# H-00488_-_Ethernet_Switch.net
KiCad netlist of a schematic drawn in Altium Designer
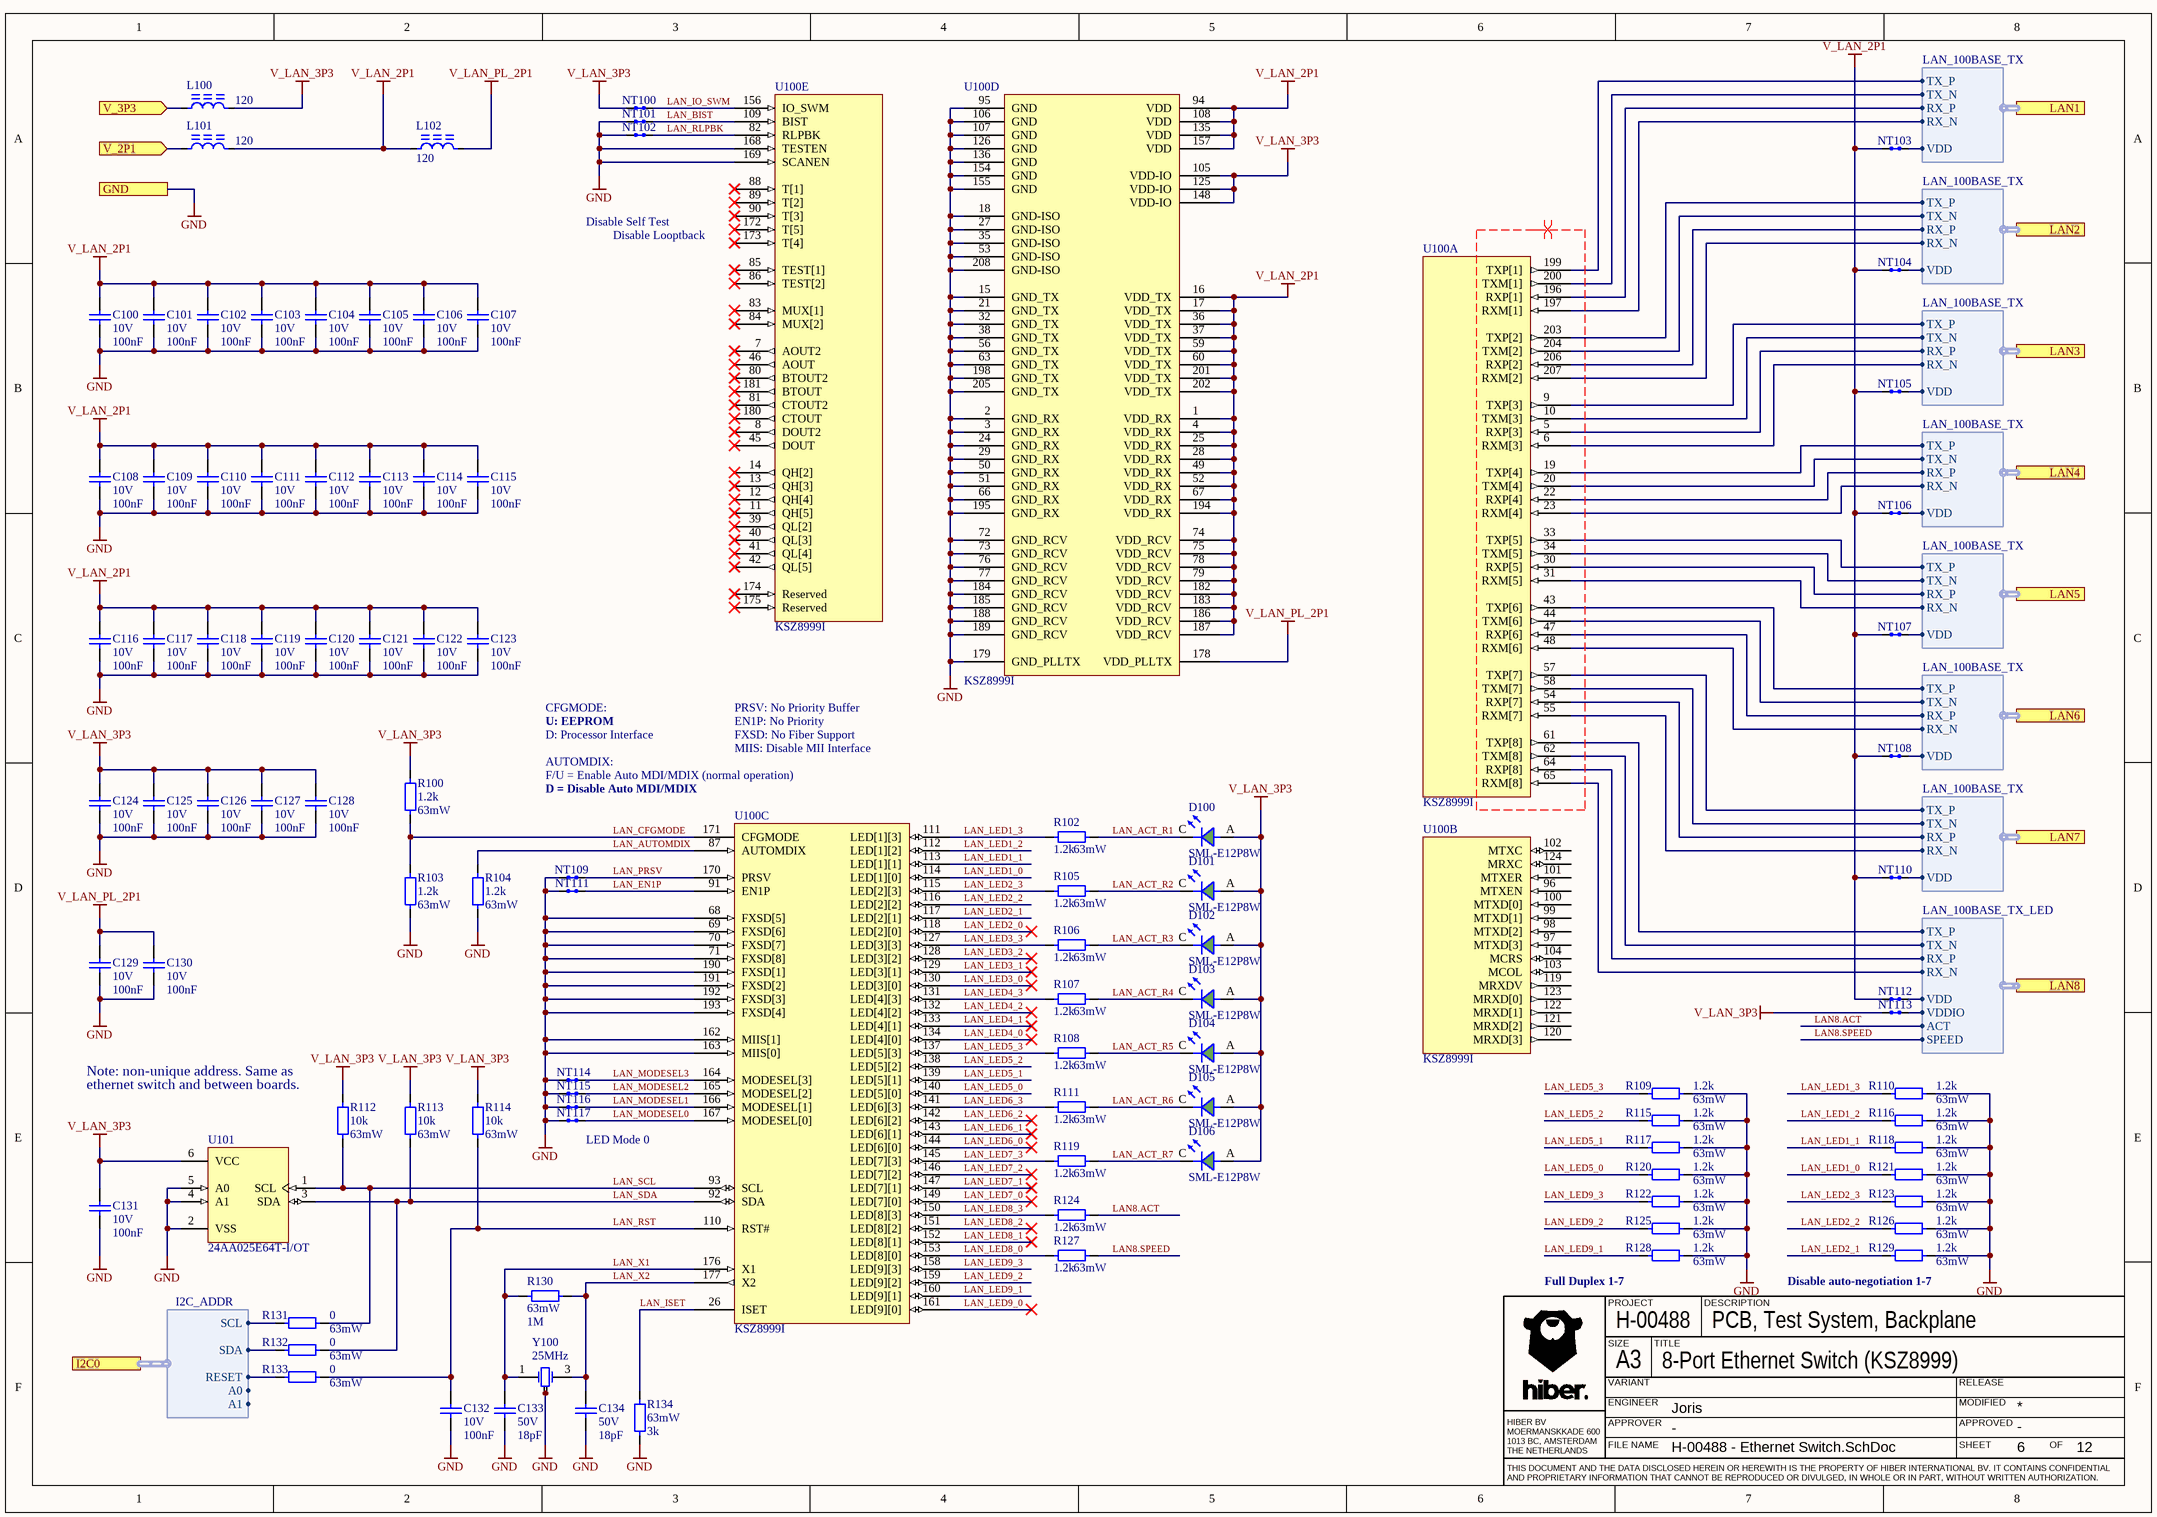
[diagram p0: H-00488 - Ethernet Switch.SchDoc]

(export (version "E")
  (design (tool "Eeschema 10.0.6"))
  (components
    (comp (ref "C100")
      (value "100nF")
      (footprint "CAPC100X50X55L30N")
      (description "CAP Standard 0402 (1005) 100,0nF 10V X7R (Standard)")
      (fields
        (field (name "RATED VOLTAGE") "10V")
        (field (name "TOLERANCE") "10%")
        (field (name "Comment") "C0402C104K8RACTU")
      )
      (libsource (lib "Hiber Vault") (part "CAPACITOR"))
    )
    (comp (ref "C101")
      (value "100nF")
      (footprint "CAPC100X50X55L30N")
      (description "CAP Standard 0402 (1005) 100,0nF 10V X7R (Standard)")
      (fields
        (field (name "RATED VOLTAGE") "10V")
        (field (name "TOLERANCE") "10%")
        (field (name "Comment") "C0402C104K8RACTU")
      )
      (libsource (lib "Hiber Vault") (part "CAPACITOR"))
    )
    (comp (ref "C102")
      (value "100nF")
      (footprint "CAPC100X50X55L30N")
      (description "CAP Standard 0402 (1005) 100,0nF 10V X7R (Standard)")
      (fields
        (field (name "RATED VOLTAGE") "10V")
        (field (name "TOLERANCE") "10%")
        (field (name "Comment") "C0402C104K8RACTU")
      )
      (libsource (lib "Hiber Vault") (part "CAPACITOR"))
    )
    (comp (ref "C103")
      (value "100nF")
      (footprint "CAPC100X50X55L30N")
      (description "CAP Standard 0402 (1005) 100,0nF 10V X7R (Standard)")
      (fields
        (field (name "RATED VOLTAGE") "10V")
        (field (name "TOLERANCE") "10%")
        (field (name "Comment") "C0402C104K8RACTU")
      )
      (libsource (lib "Hiber Vault") (part "CAPACITOR"))
    )
    (comp (ref "C104")
      (value "100nF")
      (footprint "CAPC100X50X55L30N")
      (description "CAP Standard 0402 (1005) 100,0nF 10V X7R (Standard)")
      (fields
        (field (name "RATED VOLTAGE") "10V")
        (field (name "TOLERANCE") "10%")
        (field (name "Comment") "C0402C104K8RACTU")
      )
      (libsource (lib "Hiber Vault") (part "CAPACITOR"))
    )
    (comp (ref "C105")
      (value "100nF")
      (footprint "CAPC100X50X55L30N")
      (description "CAP Standard 0402 (1005) 100,0nF 10V X7R (Standard)")
      (fields
        (field (name "RATED VOLTAGE") "10V")
        (field (name "TOLERANCE") "10%")
        (field (name "Comment") "C0402C104K8RACTU")
      )
      (libsource (lib "Hiber Vault") (part "CAPACITOR"))
    )
    (comp (ref "C106")
      (value "100nF")
      (footprint "CAPC100X50X55L30N")
      (description "CAP Standard 0402 (1005) 100,0nF 10V X7R (Standard)")
      (fields
        (field (name "RATED VOLTAGE") "10V")
        (field (name "TOLERANCE") "10%")
        (field (name "Comment") "C0402C104K8RACTU")
      )
      (libsource (lib "Hiber Vault") (part "CAPACITOR"))
    )
    (comp (ref "C107")
      (value "100nF")
      (footprint "CAPC100X50X55L30N")
      (description "CAP Standard 0402 (1005) 100,0nF 10V X7R (Standard)")
      (fields
        (field (name "RATED VOLTAGE") "10V")
        (field (name "TOLERANCE") "10%")
        (field (name "Comment") "C0402C104K8RACTU")
      )
      (libsource (lib "Hiber Vault") (part "CAPACITOR"))
    )
    (comp (ref "C108")
      (value "100nF")
      (footprint "CAPC100X50X55L30N")
      (description "CAP Standard 0402 (1005) 100,0nF 10V X7R (Standard)")
      (fields
        (field (name "RATED VOLTAGE") "10V")
        (field (name "TOLERANCE") "10%")
        (field (name "Comment") "C0402C104K8RACTU")
      )
      (libsource (lib "Hiber Vault") (part "CAPACITOR"))
    )
    (comp (ref "C109")
      (value "100nF")
      (footprint "CAPC100X50X55L30N")
      (description "CAP Standard 0402 (1005) 100,0nF 10V X7R (Standard)")
      (fields
        (field (name "RATED VOLTAGE") "10V")
        (field (name "TOLERANCE") "10%")
        (field (name "Comment") "C0402C104K8RACTU")
      )
      (libsource (lib "Hiber Vault") (part "CAPACITOR"))
    )
    (comp (ref "C110")
      (value "100nF")
      (footprint "CAPC100X50X55L30N")
      (description "CAP Standard 0402 (1005) 100,0nF 10V X7R (Standard)")
      (fields
        (field (name "RATED VOLTAGE") "10V")
        (field (name "TOLERANCE") "10%")
        (field (name "Comment") "C0402C104K8RACTU")
      )
      (libsource (lib "Hiber Vault") (part "CAPACITOR"))
    )
    (comp (ref "C111")
      (value "100nF")
      (footprint "CAPC100X50X55L30N")
      (description "CAP Standard 0402 (1005) 100,0nF 10V X7R (Standard)")
      (fields
        (field (name "RATED VOLTAGE") "10V")
        (field (name "TOLERANCE") "10%")
        (field (name "Comment") "C0402C104K8RACTU")
      )
      (libsource (lib "Hiber Vault") (part "CAPACITOR"))
    )
    (comp (ref "C112")
      (value "100nF")
      (footprint "CAPC100X50X55L30N")
      (description "CAP Standard 0402 (1005) 100,0nF 10V X7R (Standard)")
      (fields
        (field (name "RATED VOLTAGE") "10V")
        (field (name "TOLERANCE") "10%")
        (field (name "Comment") "C0402C104K8RACTU")
      )
      (libsource (lib "Hiber Vault") (part "CAPACITOR"))
    )
    (comp (ref "C113")
      (value "100nF")
      (footprint "CAPC100X50X55L30N")
      (description "CAP Standard 0402 (1005) 100,0nF 10V X7R (Standard)")
      (fields
        (field (name "RATED VOLTAGE") "10V")
        (field (name "TOLERANCE") "10%")
        (field (name "Comment") "C0402C104K8RACTU")
      )
      (libsource (lib "Hiber Vault") (part "CAPACITOR"))
    )
    (comp (ref "C114")
      (value "100nF")
      (footprint "CAPC100X50X55L30N")
      (description "CAP Standard 0402 (1005) 100,0nF 10V X7R (Standard)")
      (fields
        (field (name "RATED VOLTAGE") "10V")
        (field (name "TOLERANCE") "10%")
        (field (name "Comment") "C0402C104K8RACTU")
      )
      (libsource (lib "Hiber Vault") (part "CAPACITOR"))
    )
    (comp (ref "C115")
      (value "100nF")
      (footprint "CAPC100X50X55L30N")
      (description "CAP Standard 0402 (1005) 100,0nF 10V X7R (Standard)")
      (fields
        (field (name "RATED VOLTAGE") "10V")
        (field (name "TOLERANCE") "10%")
        (field (name "Comment") "C0402C104K8RACTU")
      )
      (libsource (lib "Hiber Vault") (part "CAPACITOR"))
    )
    (comp (ref "C116")
      (value "100nF")
      (footprint "CAPC100X50X55L30N")
      (description "CAP Standard 0402 (1005) 100,0nF 10V X7R (Standard)")
      (fields
        (field (name "RATED VOLTAGE") "10V")
        (field (name "TOLERANCE") "10%")
        (field (name "Comment") "C0402C104K8RACTU")
      )
      (libsource (lib "Hiber Vault") (part "CAPACITOR"))
    )
    (comp (ref "C117")
      (value "100nF")
      (footprint "CAPC100X50X55L30N")
      (description "CAP Standard 0402 (1005) 100,0nF 10V X7R (Standard)")
      (fields
        (field (name "RATED VOLTAGE") "10V")
        (field (name "TOLERANCE") "10%")
        (field (name "Comment") "C0402C104K8RACTU")
      )
      (libsource (lib "Hiber Vault") (part "CAPACITOR"))
    )
    (comp (ref "C118")
      (value "100nF")
      (footprint "CAPC100X50X55L30N")
      (description "CAP Standard 0402 (1005) 100,0nF 10V X7R (Standard)")
      (fields
        (field (name "RATED VOLTAGE") "10V")
        (field (name "TOLERANCE") "10%")
        (field (name "Comment") "C0402C104K8RACTU")
      )
      (libsource (lib "Hiber Vault") (part "CAPACITOR"))
    )
    (comp (ref "C119")
      (value "100nF")
      (footprint "CAPC100X50X55L30N")
      (description "CAP Standard 0402 (1005) 100,0nF 10V X7R (Standard)")
      (fields
        (field (name "RATED VOLTAGE") "10V")
        (field (name "TOLERANCE") "10%")
        (field (name "Comment") "C0402C104K8RACTU")
      )
      (libsource (lib "Hiber Vault") (part "CAPACITOR"))
    )
    (comp (ref "C120")
      (value "100nF")
      (footprint "CAPC100X50X55L30N")
      (description "CAP Standard 0402 (1005) 100,0nF 10V X7R (Standard)")
      (fields
        (field (name "RATED VOLTAGE") "10V")
        (field (name "TOLERANCE") "10%")
        (field (name "Comment") "C0402C104K8RACTU")
      )
      (libsource (lib "Hiber Vault") (part "CAPACITOR"))
    )
    (comp (ref "C121")
      (value "100nF")
      (footprint "CAPC100X50X55L30N")
      (description "CAP Standard 0402 (1005) 100,0nF 10V X7R (Standard)")
      (fields
        (field (name "RATED VOLTAGE") "10V")
        (field (name "TOLERANCE") "10%")
        (field (name "Comment") "C0402C104K8RACTU")
      )
      (libsource (lib "Hiber Vault") (part "CAPACITOR"))
    )
    (comp (ref "C122")
      (value "100nF")
      (footprint "CAPC100X50X55L30N")
      (description "CAP Standard 0402 (1005) 100,0nF 10V X7R (Standard)")
      (fields
        (field (name "RATED VOLTAGE") "10V")
        (field (name "TOLERANCE") "10%")
        (field (name "Comment") "C0402C104K8RACTU")
      )
      (libsource (lib "Hiber Vault") (part "CAPACITOR"))
    )
    (comp (ref "C123")
      (value "100nF")
      (footprint "CAPC100X50X55L30N")
      (description "CAP Standard 0402 (1005) 100,0nF 10V X7R (Standard)")
      (fields
        (field (name "RATED VOLTAGE") "10V")
        (field (name "TOLERANCE") "10%")
        (field (name "Comment") "C0402C104K8RACTU")
      )
      (libsource (lib "Hiber Vault") (part "CAPACITOR"))
    )
    (comp (ref "C124")
      (value "100nF")
      (footprint "CAPC100X50X55L30N")
      (description "CAP Standard 0402 (1005) 100,0nF 10V X7R (Standard)")
      (fields
        (field (name "RATED VOLTAGE") "10V")
        (field (name "TOLERANCE") "10%")
        (field (name "Comment") "C0402C104K8RACTU")
      )
      (libsource (lib "Hiber Vault") (part "CAPACITOR"))
    )
    (comp (ref "C125")
      (value "100nF")
      (footprint "CAPC100X50X55L30N")
      (description "CAP Standard 0402 (1005) 100,0nF 10V X7R (Standard)")
      (fields
        (field (name "RATED VOLTAGE") "10V")
        (field (name "TOLERANCE") "10%")
        (field (name "Comment") "C0402C104K8RACTU")
      )
      (libsource (lib "Hiber Vault") (part "CAPACITOR"))
    )
    (comp (ref "C126")
      (value "100nF")
      (footprint "CAPC100X50X55L30N")
      (description "CAP Standard 0402 (1005) 100,0nF 10V X7R (Standard)")
      (fields
        (field (name "RATED VOLTAGE") "10V")
        (field (name "TOLERANCE") "10%")
        (field (name "Comment") "C0402C104K8RACTU")
      )
      (libsource (lib "Hiber Vault") (part "CAPACITOR"))
    )
    (comp (ref "C127")
      (value "100nF")
      (footprint "CAPC100X50X55L30N")
      (description "CAP Standard 0402 (1005) 100,0nF 10V X7R (Standard)")
      (fields
        (field (name "RATED VOLTAGE") "10V")
        (field (name "TOLERANCE") "10%")
        (field (name "Comment") "C0402C104K8RACTU")
      )
      (libsource (lib "Hiber Vault") (part "CAPACITOR"))
    )
    (comp (ref "C128")
      (value "100nF")
      (footprint "CAPC100X50X55L30N")
      (description "CAP Standard 0402 (1005) 100,0nF 10V X7R (Standard)")
      (fields
        (field (name "RATED VOLTAGE") "10V")
        (field (name "TOLERANCE") "10%")
        (field (name "Comment") "C0402C104K8RACTU")
      )
      (libsource (lib "Hiber Vault") (part "CAPACITOR"))
    )
    (comp (ref "C129")
      (value "100nF")
      (footprint "CAPC100X50X55L30N")
      (description "CAP Standard 0402 (1005) 100,0nF 10V X7R (Standard)")
      (fields
        (field (name "RATED VOLTAGE") "10V")
        (field (name "TOLERANCE") "10%")
        (field (name "Comment") "C0402C104K8RACTU")
      )
      (libsource (lib "Hiber Vault") (part "CAPACITOR"))
    )
    (comp (ref "C130")
      (value "100nF")
      (footprint "CAPC100X50X55L30N")
      (description "CAP Standard 0402 (1005) 100,0nF 10V X7R (Standard)")
      (fields
        (field (name "RATED VOLTAGE") "10V")
        (field (name "TOLERANCE") "10%")
        (field (name "Comment") "C0402C104K8RACTU")
      )
      (libsource (lib "Hiber Vault") (part "CAPACITOR"))
    )
    (comp (ref "C131")
      (value "100nF")
      (footprint "CAPC100X50X55L30N")
      (description "CAP Standard 0402 (1005) 100,0nF 10V X7R (Standard)")
      (fields
        (field (name "RATED VOLTAGE") "10V")
        (field (name "TOLERANCE") "10%")
        (field (name "Comment") "C0402C104K8RACTU")
      )
      (libsource (lib "Hiber Vault") (part "CAPACITOR"))
    )
    (comp (ref "C132")
      (value "100nF")
      (footprint "CAPC100X50X55L30N")
      (description "CAP Standard 0402 (1005) 100,0nF 10V X7R (Standard)")
      (fields
        (field (name "RATED VOLTAGE") "10V")
        (field (name "TOLERANCE") "10%")
        (field (name "Comment") "C0402C104K8RACTU")
      )
      (libsource (lib "Hiber Vault") (part "CAPACITOR"))
    )
    (comp (ref "C133")
      (value "18pF")
      (footprint "CAPC100X50X55L30N")
      (description "CAP Standard 0402 (1005) 18,0pF 50V C0G (Standard)")
      (fields
        (field (name "RATED VOLTAGE") "50V")
        (field (name "TOLERANCE") "5%")
        (field (name "Comment") "C0402C180J5GACTU")
      )
      (libsource (lib "Hiber") (part "CAPACITOR"))
    )
    (comp (ref "C134")
      (value "18pF")
      (footprint "CAPC100X50X55L30N")
      (description "CAP Standard 0402 (1005) 18,0pF 50V C0G (Standard)")
      (fields
        (field (name "RATED VOLTAGE") "50V")
        (field (name "TOLERANCE") "5%")
        (field (name "Comment") "C0402C180J5GACTU")
      )
      (libsource (lib "Hiber") (part "CAPACITOR"))
    )
    (comp (ref "D100")
      (value "SML-E12P8W")
      (footprint "LEDC170X80X80L20_GREEN")
      (description "LED Green Diffused 0603 SMD")
      (libsource (lib "Hiber") (part "DIODE-LED-GREEN"))
    )
    (comp (ref "D101")
      (value "SML-E12P8W")
      (footprint "LEDC170X80X80L20_GREEN")
      (description "LED Green Diffused 0603 SMD")
      (libsource (lib "Hiber") (part "DIODE-LED-GREEN"))
    )
    (comp (ref "D102")
      (value "SML-E12P8W")
      (footprint "LEDC170X80X80L20_GREEN")
      (description "LED Green Diffused 0603 SMD")
      (libsource (lib "Hiber") (part "DIODE-LED-GREEN"))
    )
    (comp (ref "D103")
      (value "SML-E12P8W")
      (footprint "LEDC170X80X80L20_GREEN")
      (description "LED Green Diffused 0603 SMD")
      (libsource (lib "Hiber") (part "DIODE-LED-GREEN"))
    )
    (comp (ref "D104")
      (value "SML-E12P8W")
      (footprint "LEDC170X80X80L20_GREEN")
      (description "LED Green Diffused 0603 SMD")
      (libsource (lib "Hiber") (part "DIODE-LED-GREEN"))
    )
    (comp (ref "D105")
      (value "SML-E12P8W")
      (footprint "LEDC170X80X80L20_GREEN")
      (description "LED Green Diffused 0603 SMD")
      (libsource (lib "Hiber") (part "DIODE-LED-GREEN"))
    )
    (comp (ref "D106")
      (value "SML-E12P8W")
      (footprint "LEDC170X80X80L20_GREEN")
      (description "LED Green Diffused 0603 SMD")
      (libsource (lib "Hiber") (part "DIODE-LED-GREEN"))
    )
    (comp (ref "L100")
      (value "BLM18PG121SN1D")
      (footprint "BEADC160X80X95L30")
      (description "IND, Automotive, Chip Ferrite Bead, Power Lines, 0603, 120R, 2A")
      (fields (field (name "IMPEDANCE") "120") (field (name "TOLERANCE") "25%"))
      (libsource (lib "Hiber") (part "INDUCTOR-FERRITE"))
    )
    (comp (ref "L101")
      (value "BLM18PG121SN1D")
      (footprint "BEADC160X80X95L30")
      (description "IND, Automotive, Chip Ferrite Bead, Power Lines, 0603, 120R, 2A")
      (fields (field (name "IMPEDANCE") "120") (field (name "TOLERANCE") "25%"))
      (libsource (lib "Hiber") (part "INDUCTOR-FERRITE"))
    )
    (comp (ref "L102")
      (value "BLM18PG121SN1D")
      (footprint "BEADC160X80X95L30")
      (description "IND, Automotive, Chip Ferrite Bead, Power Lines, 0603, 120R, 2A")
      (fields (field (name "IMPEDANCE") "120") (field (name "TOLERANCE") "25%"))
      (libsource (lib "Hiber") (part "INDUCTOR-FERRITE"))
    )
    (comp (ref "NT100")
      (value "NET-TIE")
      (footprint "NT200")
      (description "Net Tie, Inline")
      (libsource (lib "Hiber") (part "NET-TIE"))
    )
    (comp (ref "NT101")
      (value "NET-TIE")
      (footprint "NT200")
      (description "Net Tie, Inline")
      (libsource (lib "Hiber") (part "NET-TIE"))
    )
    (comp (ref "NT102")
      (value "NET-TIE")
      (footprint "NT200")
      (description "Net Tie, Inline")
      (libsource (lib "Hiber") (part "NET-TIE"))
    )
    (comp (ref "NT103")
      (value "NET-TIE")
      (footprint "NT200")
      (description "Net Tie, Inline")
      (libsource (lib "Hiber") (part "NET-TIE"))
    )
    (comp (ref "NT104")
      (value "NET-TIE")
      (footprint "NT200")
      (description "Net Tie, Inline")
      (libsource (lib "Hiber") (part "NET-TIE"))
    )
    (comp (ref "NT105")
      (value "NET-TIE")
      (footprint "NT200")
      (description "Net Tie, Inline")
      (libsource (lib "Hiber") (part "NET-TIE"))
    )
    (comp (ref "NT106")
      (value "NET-TIE")
      (footprint "NT200")
      (description "Net Tie, Inline")
      (libsource (lib "Hiber") (part "NET-TIE"))
    )
    (comp (ref "NT107")
      (value "NET-TIE")
      (footprint "NT200")
      (description "Net Tie, Inline")
      (libsource (lib "Hiber") (part "NET-TIE"))
    )
    (comp (ref "NT108")
      (value "NET-TIE")
      (footprint "NT200")
      (description "Net Tie, Inline")
      (libsource (lib "Hiber") (part "NET-TIE"))
    )
    (comp (ref "NT109")
      (value "NET-TIE")
      (footprint "NT200")
      (description "Net Tie, Inline")
      (libsource (lib "Hiber") (part "NET-TIE"))
    )
    (comp (ref "NT110")
      (value "NET-TIE")
      (footprint "NT200")
      (description "Net Tie, Inline")
      (libsource (lib "Hiber") (part "NET-TIE"))
    )
    (comp (ref "NT111")
      (value "NET-TIE")
      (footprint "NT200")
      (description "Net Tie, Inline")
      (libsource (lib "Hiber") (part "NET-TIE"))
    )
    (comp (ref "NT112")
      (value "NET-TIE")
      (footprint "NT200")
      (description "Net Tie, Inline")
      (libsource (lib "Hiber") (part "NET-TIE"))
    )
    (comp (ref "NT113")
      (value "NET-TIE")
      (footprint "NT200")
      (description "Net Tie, Inline")
      (libsource (lib "Hiber") (part "NET-TIE"))
    )
    (comp (ref "NT114")
      (value "NET-TIE")
      (footprint "NT200")
      (description "Net Tie, Inline")
      (libsource (lib "Hiber") (part "NET-TIE"))
    )
    (comp (ref "NT115")
      (value "NET-TIE")
      (footprint "NT200")
      (description "Net Tie, Inline")
      (libsource (lib "Hiber") (part "NET-TIE"))
    )
    (comp (ref "NT116")
      (value "NET-TIE")
      (footprint "NT200")
      (description "Net Tie, Inline")
      (libsource (lib "Hiber") (part "NET-TIE"))
    )
    (comp (ref "NT117")
      (value "NET-TIE")
      (footprint "NT200")
      (description "Net Tie, Inline")
      (libsource (lib "Hiber") (part "NET-TIE"))
    )
    (comp (ref "R100")
      (value "1.2k")
      (footprint "RESC100X50X40L25N")
      (description "RES Standard Thick Film 0402 1K20 ±1% 0,063W")
      (fields
        (field (name "TOLERANCE") "1%")
        (field (name "RATED POWER") "63mW")
        (field (name "Comment") "CRCW04021K20FKED")
      )
      (libsource (lib "Hiber") (part "RESISTOR-2P"))
    )
    (comp (ref "R102")
      (value "1.2k")
      (footprint "RESC100X50X40L25N")
      (description "RES Standard Thick Film 0402 1K20 ±1% 0,063W")
      (fields
        (field (name "RATED POWER") "63mW")
        (field (name "TOLERANCE") "1%")
        (field (name "Comment") "CRCW04021K20FKED")
      )
      (libsource (lib "Hiber") (part "RESISTOR-2P"))
    )
    (comp (ref "R103")
      (value "1.2k")
      (footprint "RESC100X50X40L25N")
      (description "RES Standard Thick Film 0402 1K20 ±1% 0,063W")
      (fields
        (field (name "TOLERANCE") "1%")
        (field (name "RATED POWER") "63mW")
        (field (name "Comment") "CRCW04021K20FKED")
      )
      (libsource (lib "Hiber") (part "RESISTOR-2P"))
    )
    (comp (ref "R104")
      (value "1.2k")
      (footprint "RESC100X50X40L25N")
      (description "RES Standard Thick Film 0402 1K20 ±1% 0,063W")
      (fields
        (field (name "TOLERANCE") "1%")
        (field (name "RATED POWER") "63mW")
        (field (name "Comment") "CRCW04021K20FKED")
      )
      (libsource (lib "Hiber") (part "RESISTOR-2P"))
    )
    (comp (ref "R105")
      (value "1.2k")
      (footprint "RESC100X50X40L25N")
      (description "RES Standard Thick Film 0402 1K20 ±1% 0,063W")
      (fields
        (field (name "RATED POWER") "63mW")
        (field (name "TOLERANCE") "1%")
        (field (name "Comment") "CRCW04021K20FKED")
      )
      (libsource (lib "Hiber") (part "RESISTOR-2P"))
    )
    (comp (ref "R106")
      (value "1.2k")
      (footprint "RESC100X50X40L25N")
      (description "RES Standard Thick Film 0402 1K20 ±1% 0,063W")
      (fields
        (field (name "RATED POWER") "63mW")
        (field (name "TOLERANCE") "1%")
        (field (name "Comment") "CRCW04021K20FKED")
      )
      (libsource (lib "Hiber") (part "RESISTOR-2P"))
    )
    (comp (ref "R107")
      (value "1.2k")
      (footprint "RESC100X50X40L25N")
      (description "RES Standard Thick Film 0402 1K20 ±1% 0,063W")
      (fields
        (field (name "RATED POWER") "63mW")
        (field (name "TOLERANCE") "1%")
        (field (name "Comment") "CRCW04021K20FKED")
      )
      (libsource (lib "Hiber") (part "RESISTOR-2P"))
    )
    (comp (ref "R108")
      (value "1.2k")
      (footprint "RESC100X50X40L25N")
      (description "RES Standard Thick Film 0402 1K20 ±1% 0,063W")
      (fields
        (field (name "RATED POWER") "63mW")
        (field (name "TOLERANCE") "1%")
        (field (name "Comment") "CRCW04021K20FKED")
      )
      (libsource (lib "Hiber") (part "RESISTOR-2P"))
    )
    (comp (ref "R109")
      (value "1.2k")
      (footprint "RESC100X50X40L25N")
      (description "RES Standard Thick Film 0402 1K20 ±1% 0,063W")
      (fields
        (field (name "TOLERANCE") "1%")
        (field (name "RATED POWER") "63mW")
        (field (name "Comment") "CRCW04021K20FKED")
      )
      (libsource (lib "Hiber") (part "RESISTOR-2P"))
    )
    (comp (ref "R110")
      (value "1.2k")
      (footprint "RESC100X50X40L25N")
      (description "RES Standard Thick Film 0402 1K20 ±1% 0,063W")
      (fields
        (field (name "TOLERANCE") "1%")
        (field (name "RATED POWER") "63mW")
        (field (name "Comment") "CRCW04021K20FKED")
      )
      (libsource (lib "Hiber") (part "RESISTOR-2P"))
    )
    (comp (ref "R111")
      (value "1.2k")
      (footprint "RESC100X50X40L25N")
      (description "RES Standard Thick Film 0402 1K20 ±1% 0,063W")
      (fields
        (field (name "RATED POWER") "63mW")
        (field (name "TOLERANCE") "1%")
        (field (name "Comment") "CRCW04021K20FKED")
      )
      (libsource (lib "Hiber") (part "RESISTOR-2P"))
    )
    (comp (ref "R112")
      (value "10k")
      (footprint "RESC100X50X40L25N")
      (description "RES Standard Thick Film 0402 10K0 ±1% 0,063W")
      (fields
        (field (name "TOLERANCE") "1%")
        (field (name "RATED POWER") "63mW")
        (field (name "Comment") "CRCW040210K0FKED")
      )
      (libsource (lib "Hiber") (part "RESISTOR-2P"))
    )
    (comp (ref "R113")
      (value "10k")
      (footprint "RESC100X50X40L25N")
      (description "RES Standard Thick Film 0402 10K0 ±1% 0,063W")
      (fields
        (field (name "TOLERANCE") "1%")
        (field (name "RATED POWER") "63mW")
        (field (name "Comment") "CRCW040210K0FKED")
      )
      (libsource (lib "Hiber") (part "RESISTOR-2P"))
    )
    (comp (ref "R114")
      (value "10k")
      (footprint "RESC100X50X40L25N")
      (description "RES Standard Thick Film 0402 10K0 ±1% 0,063W")
      (fields
        (field (name "TOLERANCE") "1%")
        (field (name "RATED POWER") "63mW")
        (field (name "Comment") "CRCW040210K0FKED")
      )
      (libsource (lib "Hiber") (part "RESISTOR-2P"))
    )
    (comp (ref "R115")
      (value "1.2k")
      (footprint "RESC100X50X40L25N")
      (description "RES Standard Thick Film 0402 1K20 ±1% 0,063W")
      (fields
        (field (name "TOLERANCE") "1%")
        (field (name "RATED POWER") "63mW")
        (field (name "Comment") "CRCW04021K20FKED")
      )
      (libsource (lib "Hiber") (part "RESISTOR-2P"))
    )
    (comp (ref "R116")
      (value "1.2k")
      (footprint "RESC100X50X40L25N")
      (description "RES Standard Thick Film 0402 1K20 ±1% 0,063W")
      (fields
        (field (name "TOLERANCE") "1%")
        (field (name "RATED POWER") "63mW")
        (field (name "Comment") "CRCW04021K20FKED")
      )
      (libsource (lib "Hiber") (part "RESISTOR-2P"))
    )
    (comp (ref "R117")
      (value "1.2k")
      (footprint "RESC100X50X40L25N")
      (description "RES Standard Thick Film 0402 1K20 ±1% 0,063W")
      (fields
        (field (name "TOLERANCE") "1%")
        (field (name "RATED POWER") "63mW")
        (field (name "Comment") "CRCW04021K20FKED")
      )
      (libsource (lib "Hiber") (part "RESISTOR-2P"))
    )
    (comp (ref "R118")
      (value "1.2k")
      (footprint "RESC100X50X40L25N")
      (description "RES Standard Thick Film 0402 1K20 ±1% 0,063W")
      (fields
        (field (name "TOLERANCE") "1%")
        (field (name "RATED POWER") "63mW")
        (field (name "Comment") "CRCW04021K20FKED")
      )
      (libsource (lib "Hiber") (part "RESISTOR-2P"))
    )
    (comp (ref "R119")
      (value "1.2k")
      (footprint "RESC100X50X40L25N")
      (description "RES Standard Thick Film 0402 1K20 ±1% 0,063W")
      (fields
        (field (name "RATED POWER") "63mW")
        (field (name "TOLERANCE") "1%")
        (field (name "Comment") "CRCW04021K20FKED")
      )
      (libsource (lib "Hiber") (part "RESISTOR-2P"))
    )
    (comp (ref "R120")
      (value "1.2k")
      (footprint "RESC100X50X40L25N")
      (description "RES Standard Thick Film 0402 1K20 ±1% 0,063W")
      (fields
        (field (name "TOLERANCE") "1%")
        (field (name "RATED POWER") "63mW")
        (field (name "Comment") "CRCW04021K20FKED")
      )
      (libsource (lib "Hiber") (part "RESISTOR-2P"))
    )
    (comp (ref "R121")
      (value "1.2k")
      (footprint "RESC100X50X40L25N")
      (description "RES Standard Thick Film 0402 1K20 ±1% 0,063W")
      (fields
        (field (name "TOLERANCE") "1%")
        (field (name "RATED POWER") "63mW")
        (field (name "Comment") "CRCW04021K20FKED")
      )
      (libsource (lib "Hiber") (part "RESISTOR-2P"))
    )
    (comp (ref "R122")
      (value "1.2k")
      (footprint "RESC100X50X40L25N")
      (description "RES Standard Thick Film 0402 1K20 ±1% 0,063W")
      (fields
        (field (name "TOLERANCE") "1%")
        (field (name "RATED POWER") "63mW")
        (field (name "Comment") "CRCW04021K20FKED")
      )
      (libsource (lib "Hiber") (part "RESISTOR-2P"))
    )
    (comp (ref "R123")
      (value "1.2k")
      (footprint "RESC100X50X40L25N")
      (description "RES Standard Thick Film 0402 1K20 ±1% 0,063W")
      (fields
        (field (name "TOLERANCE") "1%")
        (field (name "RATED POWER") "63mW")
        (field (name "Comment") "CRCW04021K20FKED")
      )
      (libsource (lib "Hiber") (part "RESISTOR-2P"))
    )
    (comp (ref "R124")
      (value "1.2k")
      (footprint "RESC100X50X40L25N")
      (description "RES Standard Thick Film 0402 1K20 ±1% 0,063W")
      (fields
        (field (name "RATED POWER") "63mW")
        (field (name "TOLERANCE") "1%")
        (field (name "Comment") "CRCW04021K20FKED")
      )
      (libsource (lib "Hiber") (part "RESISTOR-2P"))
    )
    (comp (ref "R125")
      (value "1.2k")
      (footprint "RESC100X50X40L25N")
      (description "RES Standard Thick Film 0402 1K20 ±1% 0,063W")
      (fields
        (field (name "TOLERANCE") "1%")
        (field (name "RATED POWER") "63mW")
        (field (name "Comment") "CRCW04021K20FKED")
      )
      (libsource (lib "Hiber") (part "RESISTOR-2P"))
    )
    (comp (ref "R126")
      (value "1.2k")
      (footprint "RESC100X50X40L25N")
      (description "RES Standard Thick Film 0402 1K20 ±1% 0,063W")
      (fields
        (field (name "TOLERANCE") "1%")
        (field (name "RATED POWER") "63mW")
        (field (name "Comment") "CRCW04021K20FKED")
      )
      (libsource (lib "Hiber") (part "RESISTOR-2P"))
    )
    (comp (ref "R127")
      (value "1.2k")
      (footprint "RESC100X50X40L25N")
      (description "RES Standard Thick Film 0402 1K20 ±1% 0,063W")
      (fields
        (field (name "RATED POWER") "63mW")
        (field (name "TOLERANCE") "1%")
        (field (name "Comment") "CRCW04021K20FKED")
      )
      (libsource (lib "Hiber") (part "RESISTOR-2P"))
    )
    (comp (ref "R128")
      (value "1.2k")
      (footprint "RESC100X50X40L25N")
      (description "RES Standard Thick Film 0402 1K20 ±1% 0,063W")
      (fields
        (field (name "TOLERANCE") "1%")
        (field (name "RATED POWER") "63mW")
        (field (name "Comment") "CRCW04021K20FKED")
      )
      (libsource (lib "Hiber") (part "RESISTOR-2P"))
    )
    (comp (ref "R129")
      (value "1.2k")
      (footprint "RESC100X50X40L25N")
      (description "RES Standard Thick Film 0402 1K20 ±1% 0,063W")
      (fields
        (field (name "TOLERANCE") "1%")
        (field (name "RATED POWER") "63mW")
        (field (name "Comment") "CRCW04021K20FKED")
      )
      (libsource (lib "Hiber") (part "RESISTOR-2P"))
    )
    (comp (ref "R130")
      (value "1M")
      (footprint "RESC100X50X40L25N")
      (description "RES Standard Thick Film 0402 1M00 ±1% 0,063W")
      (fields
        (field (name "RATED POWER") "63mW")
        (field (name "TOLERANCE") "1%")
        (field (name "Comment") "CRCW04021M00FKED")
      )
      (libsource (lib "Hiber") (part "RESISTOR-2P"))
    )
    (comp (ref "R131")
      (value "0")
      (footprint "RESC100X50X40L25N")
      (description "RES Standard Thick Film 0402 0R00 ±1% 0,063W")
      (fields
        (field (name "TOLERANCE") "1%")
        (field (name "RATED POWER") "63mW")
        (field (name "Comment") "CRCW04020000Z0ED")
      )
      (libsource (lib "Hiber") (part "RESISTOR-2P"))
    )
    (comp (ref "R132")
      (value "0")
      (footprint "RESC100X50X40L25N")
      (description "RES Standard Thick Film 0402 0R00 ±1% 0,063W")
      (fields
        (field (name "TOLERANCE") "1%")
        (field (name "RATED POWER") "63mW")
        (field (name "Comment") "CRCW04020000Z0ED")
      )
      (libsource (lib "Hiber") (part "RESISTOR-2P"))
    )
    (comp (ref "R133")
      (value "0")
      (footprint "RESC100X50X40L25N")
      (description "RES Standard Thick Film 0402 0R00 ±1% 0,063W")
      (fields
        (field (name "TOLERANCE") "1%")
        (field (name "RATED POWER") "63mW")
        (field (name "Comment") "CRCW04020000Z0ED")
      )
      (libsource (lib "Hiber") (part "RESISTOR-2P"))
    )
    (comp (ref "R134")
      (value "3k")
      (footprint "RESC100X50X40L25N")
      (description "RES Standard Thick Film 0402 3K00 ±1% 0,063W")
      (fields
        (field (name "RATED POWER") "63mW")
        (field (name "TOLERANCE") "1%")
        (field (name "Comment") "CRCW04023K00FKED")
      )
      (libsource (lib "Hiber") (part "RESISTOR-2P"))
    )
    (comp (ref "U100")
      (value "KSZ8999I")
      (footprint "QFP208P50_3120X3120X410L88X22N")
      (description "LAN Switching Circuit, PQFP208")
      (libsource (lib "Hiber") (part "KSZ8999I"))
    )
    (comp (ref "U101")
      (value "24AA025E64T-I/OT")
      (footprint "SOT23-6P95_270X145L35X35")
      (description "EEPROM, 256X8, Serial, CMOS, PDSO5")
      (libsource (lib "Hiber") (part "MCHP-24AA025E64_025UID-SOT-23-6"))
    )
    (comp (ref "Y100")
      (value "TSX-3225 25.0000MF10P-C0")
      (footprint "OSCCC320X250X60L90X110")
      (description "Crystal 25MHz ±10ppm (Tol) ±10ppm (Stability) 18pF FUND 40Ohm 4-Pin SMD T/R")
      (fields (field (name "FREQUENCY") "25MHz"))
      (libsource (lib "Hiber") (part "CRYSTAL-4P"))
    )
  )
  (nets
    (net (code "4") (name "/LAN8.ACT") (class "Default")
      (node (ref "R124") (pin "1") (pinfunction "1_1") (pintype "passive"))
    )
    (net (code "5") (name "/LAN8.SPEED") (class "Default")
      (node (ref "R127") (pin "1") (pinfunction "1_1") (pintype "passive"))
    )
    (net (code "6") (name "/LAN_ACT_R1") (class "Default")
      (node (ref "D100") (pin "C") (pinfunction "C_C") (pintype "passive"))
      (node (ref "R102") (pin "1") (pinfunction "1_1") (pintype "passive"))
    )
    (net (code "7") (name "/LAN_ACT_R2") (class "Default")
      (node (ref "D101") (pin "C") (pinfunction "C_C") (pintype "passive"))
      (node (ref "R105") (pin "1") (pinfunction "1_1") (pintype "passive"))
    )
    (net (code "8") (name "/LAN_ACT_R3") (class "Default")
      (node (ref "D102") (pin "C") (pinfunction "C_C") (pintype "passive"))
      (node (ref "R106") (pin "1") (pinfunction "1_1") (pintype "passive"))
    )
    (net (code "9") (name "/LAN_ACT_R4") (class "Default")
      (node (ref "D103") (pin "C") (pinfunction "C_C") (pintype "passive"))
      (node (ref "R107") (pin "1") (pinfunction "1_1") (pintype "passive"))
    )
    (net (code "10") (name "/LAN_ACT_R5") (class "Default")
      (node (ref "D104") (pin "C") (pinfunction "C_C") (pintype "passive"))
      (node (ref "R108") (pin "1") (pinfunction "1_1") (pintype "passive"))
    )
    (net (code "11") (name "/LAN_ACT_R6") (class "Default")
      (node (ref "D105") (pin "C") (pinfunction "C_C") (pintype "passive"))
      (node (ref "R111") (pin "1") (pinfunction "1_1") (pintype "passive"))
    )
    (net (code "12") (name "/LAN_ACT_R7") (class "Default")
      (node (ref "D106") (pin "C") (pinfunction "C_C") (pintype "passive"))
      (node (ref "R119") (pin "1") (pinfunction "1_1") (pintype "passive"))
    )
    (net (code "13") (name "/LAN_AUTOMDIX") (class "Default")
      (node (ref "R104") (pin "2") (pinfunction "2_2") (pintype "passive"))
      (node (ref "U100") (pin "87") (pinfunction "AUTOMDIX_87") (pintype "input"))
    )
    (net (code "14") (name "/LAN_BIST") (class "Default")
      (node (ref "NT101") (pin "2") (pinfunction "1_2") (pintype "passive"))
      (node (ref "U100") (pin "109") (pinfunction "BIST_109") (pintype "input"))
    )
    (net (code "15") (name "/LAN_CFGMODE") (class "Default")
      (node (ref "R100") (pin "2") (pinfunction "2_2") (pintype "passive"))
      (node (ref "R103") (pin "2") (pinfunction "2_2") (pintype "passive"))
      (node (ref "U100") (pin "171") (pinfunction "CFGMODE_171") (pintype "passive"))
    )
    (net (code "16") (name "/LAN_EN1P") (class "Default")
      (node (ref "NT111") (pin "2") (pinfunction "1_2") (pintype "passive"))
      (node (ref "U100") (pin "91") (pinfunction "EN1P_91") (pintype "input"))
    )
    (net (code "17") (name "/LAN_IO_SWM") (class "Default")
      (node (ref "NT100") (pin "2") (pinfunction "1_2") (pintype "passive"))
      (node (ref "U100") (pin "156") (pinfunction "IO_SWM_156") (pintype "input"))
    )
    (net (code "18") (name "/LAN_ISET") (class "Default")
      (node (ref "R134") (pin "2") (pinfunction "2_2") (pintype "passive"))
      (node (ref "U100") (pin "26") (pinfunction "ISET_26") (pintype "passive"))
    )
    (net (code "19") (name "/LAN_LED1_0") (class "Default")
      (node (ref "R121") (pin "1") (pinfunction "1_1") (pintype "passive"))
      (node (ref "U100") (pin "114") (pinfunction "LED[1][0]_114") (pintype "bidirectional"))
    )
    (net (code "20") (name "/LAN_LED1_1") (class "Default")
      (node (ref "R118") (pin "1") (pinfunction "1_1") (pintype "passive"))
      (node (ref "U100") (pin "113") (pinfunction "LED[1][1]_113") (pintype "bidirectional"))
    )
    (net (code "21") (name "/LAN_LED1_2") (class "Default")
      (node (ref "R116") (pin "1") (pinfunction "1_1") (pintype "passive"))
      (node (ref "U100") (pin "112") (pinfunction "LED[1][2]_112") (pintype "bidirectional"))
    )
    (net (code "22") (name "/LAN_LED1_3") (class "Default")
      (node (ref "R102") (pin "2") (pinfunction "2_2") (pintype "passive"))
      (node (ref "R110") (pin "1") (pinfunction "1_1") (pintype "passive"))
      (node (ref "U100") (pin "111") (pinfunction "LED[1][3]_111") (pintype "bidirectional"))
    )
    (net (code "23") (name "/LAN_LED2_0") (class "Default")
      (node (ref "U100") (pin "118") (pinfunction "LED[2][0]_118") (pintype "bidirectional+no_connect"))
    )
    (net (code "24") (name "/LAN_LED2_1") (class "Default")
      (node (ref "R129") (pin "1") (pinfunction "1_1") (pintype "passive"))
      (node (ref "U100") (pin "117") (pinfunction "LED[2][1]_117") (pintype "bidirectional"))
    )
    (net (code "25") (name "/LAN_LED2_2") (class "Default")
      (node (ref "R126") (pin "1") (pinfunction "1_1") (pintype "passive"))
      (node (ref "U100") (pin "116") (pinfunction "LED[2][2]_116") (pintype "bidirectional"))
    )
    (net (code "26") (name "/LAN_LED2_3") (class "Default")
      (node (ref "R105") (pin "2") (pinfunction "2_2") (pintype "passive"))
      (node (ref "R123") (pin "1") (pinfunction "1_1") (pintype "passive"))
      (node (ref "U100") (pin "115") (pinfunction "LED[2][3]_115") (pintype "bidirectional"))
    )
    (net (code "27") (name "/LAN_LED3_0") (class "Default")
      (node (ref "U100") (pin "130") (pinfunction "LED[3][0]_130") (pintype "bidirectional+no_connect"))
    )
    (net (code "28") (name "/LAN_LED3_1") (class "Default")
      (node (ref "U100") (pin "129") (pinfunction "LED[3][1]_129") (pintype "bidirectional+no_connect"))
    )
    (net (code "29") (name "/LAN_LED3_2") (class "Default")
      (node (ref "U100") (pin "128") (pinfunction "LED[3][2]_128") (pintype "bidirectional+no_connect"))
    )
    (net (code "30") (name "/LAN_LED3_3") (class "Default")
      (node (ref "R106") (pin "2") (pinfunction "2_2") (pintype "passive"))
      (node (ref "U100") (pin "127") (pinfunction "LED[3][3]_127") (pintype "bidirectional"))
    )
    (net (code "31") (name "/LAN_LED4_0") (class "Default")
      (node (ref "U100") (pin "134") (pinfunction "LED[4][0]_134") (pintype "bidirectional+no_connect"))
    )
    (net (code "32") (name "/LAN_LED4_1") (class "Default")
      (node (ref "U100") (pin "133") (pinfunction "LED[4][1]_133") (pintype "bidirectional+no_connect"))
    )
    (net (code "33") (name "/LAN_LED4_2") (class "Default")
      (node (ref "U100") (pin "132") (pinfunction "LED[4][2]_132") (pintype "bidirectional+no_connect"))
    )
    (net (code "34") (name "/LAN_LED4_3") (class "Default")
      (node (ref "R107") (pin "2") (pinfunction "2_2") (pintype "passive"))
      (node (ref "U100") (pin "131") (pinfunction "LED[4][3]_131") (pintype "bidirectional"))
    )
    (net (code "35") (name "/LAN_LED5_0") (class "Default")
      (node (ref "R120") (pin "1") (pinfunction "1_1") (pintype "passive"))
      (node (ref "U100") (pin "140") (pinfunction "LED[5][0]_140") (pintype "bidirectional"))
    )
    (net (code "36") (name "/LAN_LED5_1") (class "Default")
      (node (ref "R117") (pin "1") (pinfunction "1_1") (pintype "passive"))
      (node (ref "U100") (pin "139") (pinfunction "LED[5][1]_139") (pintype "bidirectional"))
    )
    (net (code "37") (name "/LAN_LED5_2") (class "Default")
      (node (ref "R115") (pin "1") (pinfunction "1_1") (pintype "passive"))
      (node (ref "U100") (pin "138") (pinfunction "LED[5][2]_138") (pintype "bidirectional"))
    )
    (net (code "38") (name "/LAN_LED5_3") (class "Default")
      (node (ref "R108") (pin "2") (pinfunction "2_2") (pintype "passive"))
      (node (ref "R109") (pin "1") (pinfunction "1_1") (pintype "passive"))
      (node (ref "U100") (pin "137") (pinfunction "LED[5][3]_137") (pintype "bidirectional"))
    )
    (net (code "39") (name "/LAN_LED6_0") (class "Default")
      (node (ref "U100") (pin "144") (pinfunction "LED[6][0]_144") (pintype "bidirectional+no_connect"))
    )
    (net (code "40") (name "/LAN_LED6_1") (class "Default")
      (node (ref "U100") (pin "143") (pinfunction "LED[6][1]_143") (pintype "bidirectional+no_connect"))
    )
    (net (code "41") (name "/LAN_LED6_2") (class "Default")
      (node (ref "U100") (pin "142") (pinfunction "LED[6][2]_142") (pintype "bidirectional+no_connect"))
    )
    (net (code "42") (name "/LAN_LED6_3") (class "Default")
      (node (ref "R111") (pin "2") (pinfunction "2_2") (pintype "passive"))
      (node (ref "U100") (pin "141") (pinfunction "LED[6][3]_141") (pintype "bidirectional"))
    )
    (net (code "43") (name "/LAN_LED7_0") (class "Default")
      (node (ref "U100") (pin "149") (pinfunction "LED[7][0]_149") (pintype "bidirectional+no_connect"))
    )
    (net (code "44") (name "/LAN_LED7_1") (class "Default")
      (node (ref "U100") (pin "147") (pinfunction "LED[7][1]_147") (pintype "bidirectional+no_connect"))
    )
    (net (code "45") (name "/LAN_LED7_2") (class "Default")
      (node (ref "U100") (pin "146") (pinfunction "LED[7][2]_146") (pintype "bidirectional+no_connect"))
    )
    (net (code "46") (name "/LAN_LED7_3") (class "Default")
      (node (ref "R119") (pin "2") (pinfunction "2_2") (pintype "passive"))
      (node (ref "U100") (pin "145") (pinfunction "LED[7][3]_145") (pintype "bidirectional"))
    )
    (net (code "47") (name "/LAN_LED8_0") (class "Default")
      (node (ref "R127") (pin "2") (pinfunction "2_2") (pintype "passive"))
      (node (ref "U100") (pin "153") (pinfunction "LED[8][0]_153") (pintype "bidirectional"))
    )
    (net (code "48") (name "/LAN_LED8_1") (class "Default")
      (node (ref "U100") (pin "152") (pinfunction "LED[8][1]_152") (pintype "bidirectional+no_connect"))
    )
    (net (code "49") (name "/LAN_LED8_2") (class "Default")
      (node (ref "U100") (pin "151") (pinfunction "LED[8][2]_151") (pintype "bidirectional+no_connect"))
    )
    (net (code "50") (name "/LAN_LED8_3") (class "Default")
      (node (ref "R124") (pin "2") (pinfunction "2_2") (pintype "passive"))
      (node (ref "U100") (pin "150") (pinfunction "LED[8][3]_150") (pintype "bidirectional"))
    )
    (net (code "51") (name "/LAN_LED9_0") (class "Default")
      (node (ref "U100") (pin "161") (pinfunction "LED[9][0]_161") (pintype "bidirectional+no_connect"))
    )
    (net (code "52") (name "/LAN_LED9_1") (class "Default")
      (node (ref "R128") (pin "1") (pinfunction "1_1") (pintype "passive"))
      (node (ref "U100") (pin "160") (pinfunction "LED[9][1]_160") (pintype "bidirectional"))
    )
    (net (code "53") (name "/LAN_LED9_2") (class "Default")
      (node (ref "R125") (pin "1") (pinfunction "1_1") (pintype "passive"))
      (node (ref "U100") (pin "159") (pinfunction "LED[9][2]_159") (pintype "bidirectional"))
    )
    (net (code "54") (name "/LAN_LED9_3") (class "Default")
      (node (ref "R122") (pin "1") (pinfunction "1_1") (pintype "passive"))
      (node (ref "U100") (pin "158") (pinfunction "LED[9][3]_158") (pintype "bidirectional"))
    )
    (net (code "55") (name "/LAN_MODESEL0") (class "Default")
      (node (ref "NT117") (pin "2") (pinfunction "1_2") (pintype "passive"))
      (node (ref "U100") (pin "167") (pinfunction "MODESEL[0]_167") (pintype "input"))
    )
    (net (code "56") (name "/LAN_MODESEL1") (class "Default")
      (node (ref "NT116") (pin "2") (pinfunction "1_2") (pintype "passive"))
      (node (ref "U100") (pin "166") (pinfunction "MODESEL[1]_166") (pintype "input"))
    )
    (net (code "57") (name "/LAN_MODESEL2") (class "Default")
      (node (ref "NT115") (pin "2") (pinfunction "1_2") (pintype "passive"))
      (node (ref "U100") (pin "165") (pinfunction "MODESEL[2]_165") (pintype "input"))
    )
    (net (code "58") (name "/LAN_MODESEL3") (class "Default")
      (node (ref "NT114") (pin "2") (pinfunction "1_2") (pintype "passive"))
      (node (ref "U100") (pin "164") (pinfunction "MODESEL[3]_164") (pintype "input"))
    )
    (net (code "59") (name "/LAN_PRSV") (class "Default")
      (node (ref "NT109") (pin "2") (pinfunction "1_2") (pintype "passive"))
      (node (ref "U100") (pin "170") (pinfunction "PRSV_170") (pintype "input"))
    )
    (net (code "60") (name "/LAN_RLPBK") (class "Default")
      (node (ref "NT102") (pin "2") (pinfunction "1_2") (pintype "passive"))
      (node (ref "U100") (pin "82") (pinfunction "RLPBK_82") (pintype "input"))
    )
    (net (code "61") (name "/LAN_RST") (class "Default")
      (node (ref "C132") (pin "1") (pinfunction "1_1") (pintype "passive"))
      (node (ref "R114") (pin "2") (pinfunction "2_2") (pintype "passive"))
      (node (ref "R133") (pin "2") (pinfunction "2_2") (pintype "passive"))
      (node (ref "U100") (pin "110") (pinfunction "RST#_110") (pintype "input"))
    )
    (net (code "62") (name "/LAN_SCL") (class "Default")
      (node (ref "R112") (pin "2") (pinfunction "2_2") (pintype "passive"))
      (node (ref "R131") (pin "1") (pinfunction "1_1") (pintype "passive"))
      (node (ref "U100") (pin "93") (pinfunction "SCL_93") (pintype "bidirectional"))
      (node (ref "U101") (pin "1") (pinfunction "SCL_1") (pintype "input"))
    )
    (net (code "63") (name "/LAN_SDA") (class "Default")
      (node (ref "R113") (pin "2") (pinfunction "2_2") (pintype "passive"))
      (node (ref "R132") (pin "1") (pinfunction "1_1") (pintype "passive"))
      (node (ref "U100") (pin "92") (pinfunction "SDA_92") (pintype "bidirectional"))
      (node (ref "U101") (pin "3") (pinfunction "SDA_3") (pintype "bidirectional"))
    )
    (net (code "64") (name "/LAN_X1") (class "Default")
      (node (ref "C133") (pin "1") (pinfunction "1_1") (pintype "passive"))
      (node (ref "R130") (pin "1") (pinfunction "1_1") (pintype "passive"))
      (node (ref "U100") (pin "176") (pinfunction "X1_176") (pintype "input"))
      (node (ref "Y100") (pin "1") (pinfunction "1_1") (pintype "passive"))
    )
    (net (code "65") (name "/LAN_X2") (class "Default")
      (node (ref "C134") (pin "1") (pinfunction "1_1") (pintype "passive"))
      (node (ref "R130") (pin "2") (pinfunction "2_2") (pintype "passive"))
      (node (ref "U100") (pin "177") (pinfunction "X2_177") (pintype "output"))
      (node (ref "Y100") (pin "3") (pinfunction "3_3") (pintype "passive"))
    )
    (net (code "66") (name "/RESET") (class "Default")
      (node (ref "R133") (pin "1") (pinfunction "1_1") (pintype "passive"))
    )
    (net (code "67") (name "/SCL") (class "Default")
      (node (ref "R131") (pin "2") (pinfunction "2_2") (pintype "passive"))
    )
    (net (code "68") (name "/SDA") (class "Default")
      (node (ref "R132") (pin "2") (pinfunction "2_2") (pintype "passive"))
    )
    (net (code "69") (name "/VDDIO") (class "Default")
      (node (ref "NT113") (pin "2") (pinfunction "1_2") (pintype "passive"))
    )
    (net (code "70") (name "/V_2P1") (class "Default")
      (node (ref "L101") (pin "1") (pinfunction "1_1") (pintype "passive"))
    )
    (net (code "71") (name "/V_3P3") (class "Default")
      (node (ref "L100") (pin "1") (pinfunction "1_1") (pintype "passive"))
    )
    (net (code "75") (name "GND") (class "Default")
      (node (ref "C100") (pin "2") (pinfunction "2_2") (pintype "passive"))
      (node (ref "C101") (pin "2") (pinfunction "2_2") (pintype "passive"))
      (node (ref "C102") (pin "2") (pinfunction "2_2") (pintype "passive"))
      (node (ref "C103") (pin "2") (pinfunction "2_2") (pintype "passive"))
      (node (ref "C104") (pin "2") (pinfunction "2_2") (pintype "passive"))
      (node (ref "C105") (pin "2") (pinfunction "2_2") (pintype "passive"))
      (node (ref "C106") (pin "2") (pinfunction "2_2") (pintype "passive"))
      (node (ref "C107") (pin "2") (pinfunction "2_2") (pintype "passive"))
      (node (ref "C108") (pin "2") (pinfunction "2_2") (pintype "passive"))
      (node (ref "C109") (pin "2") (pinfunction "2_2") (pintype "passive"))
      (node (ref "C110") (pin "2") (pinfunction "2_2") (pintype "passive"))
      (node (ref "C111") (pin "2") (pinfunction "2_2") (pintype "passive"))
      (node (ref "C112") (pin "2") (pinfunction "2_2") (pintype "passive"))
      (node (ref "C113") (pin "2") (pinfunction "2_2") (pintype "passive"))
      (node (ref "C114") (pin "2") (pinfunction "2_2") (pintype "passive"))
      (node (ref "C115") (pin "2") (pinfunction "2_2") (pintype "passive"))
      (node (ref "C116") (pin "2") (pinfunction "2_2") (pintype "passive"))
      (node (ref "C117") (pin "2") (pinfunction "2_2") (pintype "passive"))
      (node (ref "C118") (pin "2") (pinfunction "2_2") (pintype "passive"))
      (node (ref "C119") (pin "2") (pinfunction "2_2") (pintype "passive"))
      (node (ref "C120") (pin "2") (pinfunction "2_2") (pintype "passive"))
      (node (ref "C121") (pin "2") (pinfunction "2_2") (pintype "passive"))
      (node (ref "C122") (pin "2") (pinfunction "2_2") (pintype "passive"))
      (node (ref "C123") (pin "2") (pinfunction "2_2") (pintype "passive"))
      (node (ref "C124") (pin "2") (pinfunction "2_2") (pintype "passive"))
      (node (ref "C125") (pin "2") (pinfunction "2_2") (pintype "passive"))
      (node (ref "C126") (pin "2") (pinfunction "2_2") (pintype "passive"))
      (node (ref "C127") (pin "2") (pinfunction "2_2") (pintype "passive"))
      (node (ref "C128") (pin "2") (pinfunction "2_2") (pintype "passive"))
      (node (ref "C129") (pin "2") (pinfunction "2_2") (pintype "passive"))
      (node (ref "C130") (pin "2") (pinfunction "2_2") (pintype "passive"))
      (node (ref "C131") (pin "2") (pinfunction "2_2") (pintype "passive"))
      (node (ref "C132") (pin "2") (pinfunction "2_2") (pintype "passive"))
      (node (ref "C133") (pin "2") (pinfunction "2_2") (pintype "passive"))
      (node (ref "C134") (pin "2") (pinfunction "2_2") (pintype "passive"))
      (node (ref "NT101") (pin "1") (pinfunction "1_1") (pintype "passive"))
      (node (ref "NT102") (pin "1") (pinfunction "1_1") (pintype "passive"))
      (node (ref "NT109") (pin "1") (pinfunction "1_1") (pintype "passive"))
      (node (ref "NT111") (pin "1") (pinfunction "1_1") (pintype "passive"))
      (node (ref "NT114") (pin "1") (pinfunction "1_1") (pintype "passive"))
      (node (ref "NT115") (pin "1") (pinfunction "1_1") (pintype "passive"))
      (node (ref "NT116") (pin "1") (pinfunction "1_1") (pintype "passive"))
      (node (ref "NT117") (pin "1") (pinfunction "1_1") (pintype "passive"))
      (node (ref "R103") (pin "1") (pinfunction "1_1") (pintype "passive"))
      (node (ref "R104") (pin "1") (pinfunction "1_1") (pintype "passive"))
      (node (ref "R109") (pin "2") (pinfunction "2_2") (pintype "passive"))
      (node (ref "R110") (pin "2") (pinfunction "2_2") (pintype "passive"))
      (node (ref "R115") (pin "2") (pinfunction "2_2") (pintype "passive"))
      (node (ref "R116") (pin "2") (pinfunction "2_2") (pintype "passive"))
      (node (ref "R117") (pin "2") (pinfunction "2_2") (pintype "passive"))
      (node (ref "R118") (pin "2") (pinfunction "2_2") (pintype "passive"))
      (node (ref "R120") (pin "2") (pinfunction "2_2") (pintype "passive"))
      (node (ref "R121") (pin "2") (pinfunction "2_2") (pintype "passive"))
      (node (ref "R122") (pin "2") (pinfunction "2_2") (pintype "passive"))
      (node (ref "R123") (pin "2") (pinfunction "2_2") (pintype "passive"))
      (node (ref "R125") (pin "2") (pinfunction "2_2") (pintype "passive"))
      (node (ref "R126") (pin "2") (pinfunction "2_2") (pintype "passive"))
      (node (ref "R128") (pin "2") (pinfunction "2_2") (pintype "passive"))
      (node (ref "R129") (pin "2") (pinfunction "2_2") (pintype "passive"))
      (node (ref "R134") (pin "1") (pinfunction "1_1") (pintype "passive"))
      (node (ref "U100") (pin "106") (pinfunction "GND_106") (pintype "passive"))
      (node (ref "U100") (pin "107") (pinfunction "GND_107") (pintype "passive"))
      (node (ref "U100") (pin "126") (pinfunction "GND_126") (pintype "passive"))
      (node (ref "U100") (pin "136") (pinfunction "GND_136") (pintype "passive"))
      (node (ref "U100") (pin "15") (pinfunction "GND_TX_15") (pintype "passive"))
      (node (ref "U100") (pin "154") (pinfunction "GND_154") (pintype "passive"))
      (node (ref "U100") (pin "155") (pinfunction "GND_155") (pintype "passive"))
      (node (ref "U100") (pin "162") (pinfunction "MIIS[1]_162") (pintype "input"))
      (node (ref "U100") (pin "163") (pinfunction "MIIS[0]_163") (pintype "input"))
      (node (ref "U100") (pin "168") (pinfunction "TESTEN_168") (pintype "input"))
      (node (ref "U100") (pin "169") (pinfunction "SCANEN_169") (pintype "input"))
      (node (ref "U100") (pin "179") (pinfunction "GND_PLLTX_179") (pintype "passive"))
      (node (ref "U100") (pin "18") (pinfunction "GND-ISO_18") (pintype "passive"))
      (node (ref "U100") (pin "184") (pinfunction "GND_RCV_184") (pintype "passive"))
      (node (ref "U100") (pin "185") (pinfunction "GND_RCV_185") (pintype "passive"))
      (node (ref "U100") (pin "188") (pinfunction "GND_RCV_188") (pintype "passive"))
      (node (ref "U100") (pin "189") (pinfunction "GND_RCV_189") (pintype "passive"))
      (node (ref "U100") (pin "190") (pinfunction "FXSD[1]_190") (pintype "input"))
      (node (ref "U100") (pin "191") (pinfunction "FXSD[2]_191") (pintype "input"))
      (node (ref "U100") (pin "192") (pinfunction "FXSD[3]_192") (pintype "input"))
      (node (ref "U100") (pin "193") (pinfunction "FXSD[4]_193") (pintype "input"))
      (node (ref "U100") (pin "195") (pinfunction "GND_RX_195") (pintype "passive"))
      (node (ref "U100") (pin "198") (pinfunction "GND_TX_198") (pintype "passive"))
      (node (ref "U100") (pin "2") (pinfunction "GND_RX_2") (pintype "passive"))
      (node (ref "U100") (pin "205") (pinfunction "GND_TX_205") (pintype "passive"))
      (node (ref "U100") (pin "208") (pinfunction "GND-ISO_208") (pintype "passive"))
      (node (ref "U100") (pin "21") (pinfunction "GND_TX_21") (pintype "passive"))
      (node (ref "U100") (pin "24") (pinfunction "GND_RX_24") (pintype "passive"))
      (node (ref "U100") (pin "27") (pinfunction "GND-ISO_27") (pintype "passive"))
      (node (ref "U100") (pin "29") (pinfunction "GND_RX_29") (pintype "passive"))
      (node (ref "U100") (pin "3") (pinfunction "GND_RX_3") (pintype "passive"))
      (node (ref "U100") (pin "32") (pinfunction "GND_TX_32") (pintype "passive"))
      (node (ref "U100") (pin "35") (pinfunction "GND-ISO_35") (pintype "passive"))
      (node (ref "U100") (pin "38") (pinfunction "GND_TX_38") (pintype "passive"))
      (node (ref "U100") (pin "50") (pinfunction "GND_RX_50") (pintype "passive"))
      (node (ref "U100") (pin "51") (pinfunction "GND_RX_51") (pintype "passive"))
      (node (ref "U100") (pin "53") (pinfunction "GND-ISO_53") (pintype "passive"))
      (node (ref "U100") (pin "56") (pinfunction "GND_TX_56") (pintype "passive"))
      (node (ref "U100") (pin "63") (pinfunction "GND_TX_63") (pintype "passive"))
      (node (ref "U100") (pin "66") (pinfunction "GND_RX_66") (pintype "passive"))
      (node (ref "U100") (pin "68") (pinfunction "FXSD[5]_68") (pintype "input"))
      (node (ref "U100") (pin "69") (pinfunction "FXSD[6]_69") (pintype "input"))
      (node (ref "U100") (pin "70") (pinfunction "FXSD[7]_70") (pintype "input"))
      (node (ref "U100") (pin "71") (pinfunction "FXSD[8]_71") (pintype "input"))
      (node (ref "U100") (pin "72") (pinfunction "GND_RCV_72") (pintype "passive"))
      (node (ref "U100") (pin "73") (pinfunction "GND_RCV_73") (pintype "passive"))
      (node (ref "U100") (pin "76") (pinfunction "GND_RCV_76") (pintype "passive"))
      (node (ref "U100") (pin "77") (pinfunction "GND_RCV_77") (pintype "passive"))
      (node (ref "U100") (pin "95") (pinfunction "GND_95") (pintype "passive"))
      (node (ref "U101") (pin "2") (pinfunction "VSS_2") (pintype "power_in"))
      (node (ref "U101") (pin "4") (pinfunction "A1_4") (pintype "input"))
      (node (ref "U101") (pin "5") (pinfunction "A0_5") (pintype "input"))
      (node (ref "Y100") (pin "2") (pinfunction "2_2") (pintype "passive"))
      (node (ref "Y100") (pin "4") (pinfunction "4_4") (pintype "passive"))
    )
    (net (code "76") (name "V_LAN_2P1") (class "Default")
      (node (ref "C100") (pin "1") (pinfunction "1_1") (pintype "passive"))
      (node (ref "C101") (pin "1") (pinfunction "1_1") (pintype "passive"))
      (node (ref "C102") (pin "1") (pinfunction "1_1") (pintype "passive"))
      (node (ref "C103") (pin "1") (pinfunction "1_1") (pintype "passive"))
      (node (ref "C104") (pin "1") (pinfunction "1_1") (pintype "passive"))
      (node (ref "C105") (pin "1") (pinfunction "1_1") (pintype "passive"))
      (node (ref "C106") (pin "1") (pinfunction "1_1") (pintype "passive"))
      (node (ref "C107") (pin "1") (pinfunction "1_1") (pintype "passive"))
      (node (ref "C108") (pin "1") (pinfunction "1_1") (pintype "passive"))
      (node (ref "C109") (pin "1") (pinfunction "1_1") (pintype "passive"))
      (node (ref "C110") (pin "1") (pinfunction "1_1") (pintype "passive"))
      (node (ref "C111") (pin "1") (pinfunction "1_1") (pintype "passive"))
      (node (ref "C112") (pin "1") (pinfunction "1_1") (pintype "passive"))
      (node (ref "C113") (pin "1") (pinfunction "1_1") (pintype "passive"))
      (node (ref "C114") (pin "1") (pinfunction "1_1") (pintype "passive"))
      (node (ref "C115") (pin "1") (pinfunction "1_1") (pintype "passive"))
      (node (ref "C116") (pin "1") (pinfunction "1_1") (pintype "passive"))
      (node (ref "C117") (pin "1") (pinfunction "1_1") (pintype "passive"))
      (node (ref "C118") (pin "1") (pinfunction "1_1") (pintype "passive"))
      (node (ref "C119") (pin "1") (pinfunction "1_1") (pintype "passive"))
      (node (ref "C120") (pin "1") (pinfunction "1_1") (pintype "passive"))
      (node (ref "C121") (pin "1") (pinfunction "1_1") (pintype "passive"))
      (node (ref "C122") (pin "1") (pinfunction "1_1") (pintype "passive"))
      (node (ref "C123") (pin "1") (pinfunction "1_1") (pintype "passive"))
      (node (ref "L101") (pin "2") (pinfunction "2_2") (pintype "passive"))
      (node (ref "L102") (pin "1") (pinfunction "1_1") (pintype "passive"))
      (node (ref "NT103") (pin "1") (pinfunction "1_1") (pintype "passive"))
      (node (ref "NT104") (pin "1") (pinfunction "1_1") (pintype "passive"))
      (node (ref "NT105") (pin "1") (pinfunction "1_1") (pintype "passive"))
      (node (ref "NT106") (pin "1") (pinfunction "1_1") (pintype "passive"))
      (node (ref "NT107") (pin "1") (pinfunction "1_1") (pintype "passive"))
      (node (ref "NT108") (pin "1") (pinfunction "1_1") (pintype "passive"))
      (node (ref "NT110") (pin "1") (pinfunction "1_1") (pintype "passive"))
      (node (ref "NT112") (pin "1") (pinfunction "1_1") (pintype "passive"))
      (node (ref "U100") (pin "1") (pinfunction "VDD_RX_1") (pintype "power_in"))
      (node (ref "U100") (pin "108") (pinfunction "VDD_108") (pintype "power_in"))
      (node (ref "U100") (pin "135") (pinfunction "VDD_135") (pintype "power_in"))
      (node (ref "U100") (pin "157") (pinfunction "VDD_157") (pintype "power_in"))
      (node (ref "U100") (pin "16") (pinfunction "VDD_TX_16") (pintype "power_in"))
      (node (ref "U100") (pin "17") (pinfunction "VDD_TX_17") (pintype "power_in"))
      (node (ref "U100") (pin "182") (pinfunction "VDD_RCV_182") (pintype "power_in"))
      (node (ref "U100") (pin "183") (pinfunction "VDD_RCV_183") (pintype "power_in"))
      (node (ref "U100") (pin "186") (pinfunction "VDD_RCV_186") (pintype "power_in"))
      (node (ref "U100") (pin "187") (pinfunction "VDD_RCV_187") (pintype "power_in"))
      (node (ref "U100") (pin "194") (pinfunction "VDD_RX_194") (pintype "power_in"))
      (node (ref "U100") (pin "201") (pinfunction "VDD_TX_201") (pintype "power_in"))
      (node (ref "U100") (pin "202") (pinfunction "VDD_TX_202") (pintype "power_in"))
      (node (ref "U100") (pin "25") (pinfunction "VDD_RX_25") (pintype "power_in"))
      (node (ref "U100") (pin "28") (pinfunction "VDD_RX_28") (pintype "power_in"))
      (node (ref "U100") (pin "36") (pinfunction "VDD_TX_36") (pintype "power_in"))
      (node (ref "U100") (pin "37") (pinfunction "VDD_TX_37") (pintype "power_in"))
      (node (ref "U100") (pin "4") (pinfunction "VDD_RX_4") (pintype "power_in"))
      (node (ref "U100") (pin "49") (pinfunction "VDD_RX_49") (pintype "power_in"))
      (node (ref "U100") (pin "52") (pinfunction "VDD_RX_52") (pintype "power_in"))
      (node (ref "U100") (pin "59") (pinfunction "VDD_TX_59") (pintype "power_in"))
      (node (ref "U100") (pin "60") (pinfunction "VDD_TX_60") (pintype "power_in"))
      (node (ref "U100") (pin "67") (pinfunction "VDD_RX_67") (pintype "power_in"))
      (node (ref "U100") (pin "74") (pinfunction "VDD_RCV_74") (pintype "power_in"))
      (node (ref "U100") (pin "75") (pinfunction "VDD_RCV_75") (pintype "power_in"))
      (node (ref "U100") (pin "78") (pinfunction "VDD_RCV_78") (pintype "power_in"))
      (node (ref "U100") (pin "79") (pinfunction "VDD_RCV_79") (pintype "power_in"))
      (node (ref "U100") (pin "94") (pinfunction "VDD_94") (pintype "power_in"))
    )
    (net (code "77") (name "V_LAN_3P3") (class "Default")
      (node (ref "C124") (pin "1") (pinfunction "1_1") (pintype "passive"))
      (node (ref "C125") (pin "1") (pinfunction "1_1") (pintype "passive"))
      (node (ref "C126") (pin "1") (pinfunction "1_1") (pintype "passive"))
      (node (ref "C127") (pin "1") (pinfunction "1_1") (pintype "passive"))
      (node (ref "C128") (pin "1") (pinfunction "1_1") (pintype "passive"))
      (node (ref "C131") (pin "1") (pinfunction "1_1") (pintype "passive"))
      (node (ref "D100") (pin "A") (pinfunction "A_A") (pintype "passive"))
      (node (ref "D101") (pin "A") (pinfunction "A_A") (pintype "passive"))
      (node (ref "D102") (pin "A") (pinfunction "A_A") (pintype "passive"))
      (node (ref "D103") (pin "A") (pinfunction "A_A") (pintype "passive"))
      (node (ref "D104") (pin "A") (pinfunction "A_A") (pintype "passive"))
      (node (ref "D105") (pin "A") (pinfunction "A_A") (pintype "passive"))
      (node (ref "D106") (pin "A") (pinfunction "A_A") (pintype "passive"))
      (node (ref "L100") (pin "2") (pinfunction "2_2") (pintype "passive"))
      (node (ref "NT100") (pin "1") (pinfunction "1_1") (pintype "passive"))
      (node (ref "NT113") (pin "1") (pinfunction "1_1") (pintype "passive"))
      (node (ref "R100") (pin "1") (pinfunction "1_1") (pintype "passive"))
      (node (ref "R112") (pin "1") (pinfunction "1_1") (pintype "passive"))
      (node (ref "R113") (pin "1") (pinfunction "1_1") (pintype "passive"))
      (node (ref "R114") (pin "1") (pinfunction "1_1") (pintype "passive"))
      (node (ref "U100") (pin "105") (pinfunction "VDD-IO_105") (pintype "power_in"))
      (node (ref "U100") (pin "125") (pinfunction "VDD-IO_125") (pintype "power_in"))
      (node (ref "U100") (pin "148") (pinfunction "VDD-IO_148") (pintype "power_in"))
      (node (ref "U101") (pin "6") (pinfunction "VCC_6") (pintype "power_in"))
    )
    (net (code "78") (name "V_LAN_PL_2P1") (class "Default")
      (node (ref "C129") (pin "1") (pinfunction "1_1") (pintype "passive"))
      (node (ref "C130") (pin "1") (pinfunction "1_1") (pintype "passive"))
      (node (ref "L102") (pin "2") (pinfunction "2_2") (pintype "passive"))
      (node (ref "U100") (pin "178") (pinfunction "VDD_PLLTX_178") (pintype "power_in"))
    )
    (net (code "79") (name "unconnected-(NT103-1-Pad2)") (class "Default")
      (node (ref "NT103") (pin "2") (pinfunction "1_2") (pintype "passive"))
    )
    (net (code "80") (name "unconnected-(NT104-1-Pad2)") (class "Default")
      (node (ref "NT104") (pin "2") (pinfunction "1_2") (pintype "passive"))
    )
    (net (code "81") (name "unconnected-(NT105-1-Pad2)") (class "Default")
      (node (ref "NT105") (pin "2") (pinfunction "1_2") (pintype "passive"))
    )
    (net (code "82") (name "unconnected-(NT106-1-Pad2)") (class "Default")
      (node (ref "NT106") (pin "2") (pinfunction "1_2") (pintype "passive"))
    )
    (net (code "83") (name "unconnected-(NT107-1-Pad2)") (class "Default")
      (node (ref "NT107") (pin "2") (pinfunction "1_2") (pintype "passive"))
    )
    (net (code "84") (name "unconnected-(NT108-1-Pad2)") (class "Default")
      (node (ref "NT108") (pin "2") (pinfunction "1_2") (pintype "passive"))
    )
    (net (code "85") (name "unconnected-(NT110-1-Pad2)") (class "Default")
      (node (ref "NT110") (pin "2") (pinfunction "1_2") (pintype "passive"))
    )
    (net (code "86") (name "unconnected-(NT112-1-Pad2)") (class "Default")
      (node (ref "NT112") (pin "2") (pinfunction "1_2") (pintype "passive"))
    )
    (net (code "87") (name "unconnected-(U100A-RXM[1]-Pad197)") (class "Default")
      (node (ref "U100") (pin "197") (pinfunction "RXM[1]_197") (pintype "input"))
    )
    (net (code "88") (name "unconnected-(U100A-RXM[2]-Pad207)") (class "Default")
      (node (ref "U100") (pin "207") (pinfunction "RXM[2]_207") (pintype "input"))
    )
    (net (code "89") (name "unconnected-(U100A-RXM[3]-Pad6)") (class "Default")
      (node (ref "U100") (pin "6") (pinfunction "RXM[3]_6") (pintype "input"))
    )
    (net (code "90") (name "unconnected-(U100A-RXM[4]-Pad23)") (class "Default")
      (node (ref "U100") (pin "23") (pinfunction "RXM[4]_23") (pintype "input"))
    )
    (net (code "91") (name "unconnected-(U100A-RXM[5]-Pad31)") (class "Default")
      (node (ref "U100") (pin "31") (pinfunction "RXM[5]_31") (pintype "input"))
    )
    (net (code "92") (name "unconnected-(U100A-RXM[6]-Pad48)") (class "Default")
      (node (ref "U100") (pin "48") (pinfunction "RXM[6]_48") (pintype "input"))
    )
    (net (code "93") (name "unconnected-(U100A-RXM[7]-Pad55)") (class "Default")
      (node (ref "U100") (pin "55") (pinfunction "RXM[7]_55") (pintype "input"))
    )
    (net (code "94") (name "unconnected-(U100A-RXM[8]-Pad65)") (class "Default")
      (node (ref "U100") (pin "65") (pinfunction "RXM[8]_65") (pintype "input"))
    )
    (net (code "95") (name "unconnected-(U100A-RXP[1]-Pad196)") (class "Default")
      (node (ref "U100") (pin "196") (pinfunction "RXP[1]_196") (pintype "input"))
    )
    (net (code "96") (name "unconnected-(U100A-RXP[2]-Pad206)") (class "Default")
      (node (ref "U100") (pin "206") (pinfunction "RXP[2]_206") (pintype "input"))
    )
    (net (code "97") (name "unconnected-(U100A-RXP[3]-Pad5)") (class "Default")
      (node (ref "U100") (pin "5") (pinfunction "RXP[3]_5") (pintype "input"))
    )
    (net (code "98") (name "unconnected-(U100A-RXP[4]-Pad22)") (class "Default")
      (node (ref "U100") (pin "22") (pinfunction "RXP[4]_22") (pintype "input"))
    )
    (net (code "99") (name "unconnected-(U100A-RXP[5]-Pad30)") (class "Default")
      (node (ref "U100") (pin "30") (pinfunction "RXP[5]_30") (pintype "input"))
    )
    (net (code "100") (name "unconnected-(U100A-RXP[6]-Pad47)") (class "Default")
      (node (ref "U100") (pin "47") (pinfunction "RXP[6]_47") (pintype "input"))
    )
    (net (code "101") (name "unconnected-(U100A-RXP[7]-Pad54)") (class "Default")
      (node (ref "U100") (pin "54") (pinfunction "RXP[7]_54") (pintype "input"))
    )
    (net (code "102") (name "unconnected-(U100A-RXP[8]-Pad64)") (class "Default")
      (node (ref "U100") (pin "64") (pinfunction "RXP[8]_64") (pintype "input"))
    )
    (net (code "103") (name "unconnected-(U100A-TXM[1]-Pad200)") (class "Default")
      (node (ref "U100") (pin "200") (pinfunction "TXM[1]_200") (pintype "output"))
    )
    (net (code "104") (name "unconnected-(U100A-TXM[2]-Pad204)") (class "Default")
      (node (ref "U100") (pin "204") (pinfunction "TXM[2]_204") (pintype "output"))
    )
    (net (code "105") (name "unconnected-(U100A-TXM[3]-Pad10)") (class "Default")
      (node (ref "U100") (pin "10") (pinfunction "TXM[3]_10") (pintype "output"))
    )
    (net (code "106") (name "unconnected-(U100A-TXM[4]-Pad20)") (class "Default")
      (node (ref "U100") (pin "20") (pinfunction "TXM[4]_20") (pintype "output"))
    )
    (net (code "107") (name "unconnected-(U100A-TXM[5]-Pad34)") (class "Default")
      (node (ref "U100") (pin "34") (pinfunction "TXM[5]_34") (pintype "output"))
    )
    (net (code "108") (name "unconnected-(U100A-TXM[6]-Pad44)") (class "Default")
      (node (ref "U100") (pin "44") (pinfunction "TXM[6]_44") (pintype "output"))
    )
    (net (code "109") (name "unconnected-(U100A-TXM[7]-Pad58)") (class "Default")
      (node (ref "U100") (pin "58") (pinfunction "TXM[7]_58") (pintype "output"))
    )
    (net (code "110") (name "unconnected-(U100A-TXM[8]-Pad62)") (class "Default")
      (node (ref "U100") (pin "62") (pinfunction "TXM[8]_62") (pintype "output"))
    )
    (net (code "111") (name "unconnected-(U100A-TXP[1]-Pad199)") (class "Default")
      (node (ref "U100") (pin "199") (pinfunction "TXP[1]_199") (pintype "output"))
    )
    (net (code "112") (name "unconnected-(U100A-TXP[2]-Pad203)") (class "Default")
      (node (ref "U100") (pin "203") (pinfunction "TXP[2]_203") (pintype "output"))
    )
    (net (code "113") (name "unconnected-(U100A-TXP[3]-Pad9)") (class "Default")
      (node (ref "U100") (pin "9") (pinfunction "TXP[3]_9") (pintype "output"))
    )
    (net (code "114") (name "unconnected-(U100A-TXP[4]-Pad19)") (class "Default")
      (node (ref "U100") (pin "19") (pinfunction "TXP[4]_19") (pintype "output"))
    )
    (net (code "115") (name "unconnected-(U100A-TXP[5]-Pad33)") (class "Default")
      (node (ref "U100") (pin "33") (pinfunction "TXP[5]_33") (pintype "output"))
    )
    (net (code "116") (name "unconnected-(U100A-TXP[6]-Pad43)") (class "Default")
      (node (ref "U100") (pin "43") (pinfunction "TXP[6]_43") (pintype "output"))
    )
    (net (code "117") (name "unconnected-(U100A-TXP[7]-Pad57)") (class "Default")
      (node (ref "U100") (pin "57") (pinfunction "TXP[7]_57") (pintype "output"))
    )
    (net (code "118") (name "unconnected-(U100A-TXP[8]-Pad61)") (class "Default")
      (node (ref "U100") (pin "61") (pinfunction "TXP[8]_61") (pintype "output"))
    )
    (net (code "119") (name "unconnected-(U100B-MCOL-Pad103)") (class "Default")
      (node (ref "U100") (pin "103") (pinfunction "MCOL_103") (pintype "bidirectional"))
    )
    (net (code "120") (name "unconnected-(U100B-MCRS-Pad104)") (class "Default")
      (node (ref "U100") (pin "104") (pinfunction "MCRS_104") (pintype "bidirectional"))
    )
    (net (code "121") (name "unconnected-(U100B-MRXC-Pad124)") (class "Default")
      (node (ref "U100") (pin "124") (pinfunction "MRXC_124") (pintype "bidirectional"))
    )
    (net (code "122") (name "unconnected-(U100B-MRXDV-Pad119)") (class "Default")
      (node (ref "U100") (pin "119") (pinfunction "MRXDV_119") (pintype "output"))
    )
    (net (code "123") (name "unconnected-(U100B-MRXD[0]-Pad123)") (class "Default")
      (node (ref "U100") (pin "123") (pinfunction "MRXD[0]_123") (pintype "output"))
    )
    (net (code "124") (name "unconnected-(U100B-MRXD[1]-Pad122)") (class "Default")
      (node (ref "U100") (pin "122") (pinfunction "MRXD[1]_122") (pintype "output"))
    )
    (net (code "125") (name "unconnected-(U100B-MRXD[2]-Pad121)") (class "Default")
      (node (ref "U100") (pin "121") (pinfunction "MRXD[2]_121") (pintype "output"))
    )
    (net (code "126") (name "unconnected-(U100B-MRXD[3]-Pad120)") (class "Default")
      (node (ref "U100") (pin "120") (pinfunction "MRXD[3]_120") (pintype "output"))
    )
    (net (code "127") (name "unconnected-(U100B-MTXC-Pad102)") (class "Default")
      (node (ref "U100") (pin "102") (pinfunction "MTXC_102") (pintype "bidirectional"))
    )
    (net (code "128") (name "unconnected-(U100B-MTXD[0]-Pad100)") (class "Default")
      (node (ref "U100") (pin "100") (pinfunction "MTXD[0]_100") (pintype "input"))
    )
    (net (code "129") (name "unconnected-(U100B-MTXD[1]-Pad99)") (class "Default")
      (node (ref "U100") (pin "99") (pinfunction "MTXD[1]_99") (pintype "input"))
    )
    (net (code "130") (name "unconnected-(U100B-MTXD[2]-Pad98)") (class "Default")
      (node (ref "U100") (pin "98") (pinfunction "MTXD[2]_98") (pintype "input"))
    )
    (net (code "131") (name "unconnected-(U100B-MTXD[3]-Pad97)") (class "Default")
      (node (ref "U100") (pin "97") (pinfunction "MTXD[3]_97") (pintype "input"))
    )
    (net (code "132") (name "unconnected-(U100B-MTXEN-Pad96)") (class "Default")
      (node (ref "U100") (pin "96") (pinfunction "MTXEN_96") (pintype "input"))
    )
    (net (code "133") (name "unconnected-(U100B-MTXER-Pad101)") (class "Default")
      (node (ref "U100") (pin "101") (pinfunction "MTXER_101") (pintype "input"))
    )
    (net (code "134") (name "unconnected-(U100E-AOUT-Pad46)") (class "Default")
      (node (ref "U100") (pin "46") (pinfunction "AOUT_46") (pintype "output+no_connect"))
    )
    (net (code "135") (name "unconnected-(U100E-AOUT2-Pad7)") (class "Default")
      (node (ref "U100") (pin "7") (pinfunction "AOUT2_7") (pintype "output+no_connect"))
    )
    (net (code "136") (name "unconnected-(U100E-BTOUT-Pad181)") (class "Default")
      (node (ref "U100") (pin "181") (pinfunction "BTOUT_181") (pintype "output+no_connect"))
    )
    (net (code "137") (name "unconnected-(U100E-BTOUT2-Pad80)") (class "Default")
      (node (ref "U100") (pin "80") (pinfunction "BTOUT2_80") (pintype "output+no_connect"))
    )
    (net (code "138") (name "unconnected-(U100E-CTOUT-Pad180)") (class "Default")
      (node (ref "U100") (pin "180") (pinfunction "CTOUT_180") (pintype "output+no_connect"))
    )
    (net (code "139") (name "unconnected-(U100E-CTOUT2-Pad81)") (class "Default")
      (node (ref "U100") (pin "81") (pinfunction "CTOUT2_81") (pintype "output+no_connect"))
    )
    (net (code "140") (name "unconnected-(U100E-DOUT-Pad45)") (class "Default")
      (node (ref "U100") (pin "45") (pinfunction "DOUT_45") (pintype "output+no_connect"))
    )
    (net (code "141") (name "unconnected-(U100E-DOUT2-Pad8)") (class "Default")
      (node (ref "U100") (pin "8") (pinfunction "DOUT2_8") (pintype "output+no_connect"))
    )
    (net (code "142") (name "unconnected-(U100E-MUX[1]-Pad83)") (class "Default")
      (node (ref "U100") (pin "83") (pinfunction "MUX[1]_83") (pintype "input+no_connect"))
    )
    (net (code "143") (name "unconnected-(U100E-MUX[2]-Pad84)") (class "Default")
      (node (ref "U100") (pin "84") (pinfunction "MUX[2]_84") (pintype "input+no_connect"))
    )
    (net (code "144") (name "unconnected-(U100E-QH[2]-Pad14)") (class "Default")
      (node (ref "U100") (pin "14") (pinfunction "QH[2]_14") (pintype "output+no_connect"))
    )
    (net (code "145") (name "unconnected-(U100E-QH[3]-Pad13)") (class "Default")
      (node (ref "U100") (pin "13") (pinfunction "QH[3]_13") (pintype "output+no_connect"))
    )
    (net (code "146") (name "unconnected-(U100E-QH[4]-Pad12)") (class "Default")
      (node (ref "U100") (pin "12") (pinfunction "QH[4]_12") (pintype "output+no_connect"))
    )
    (net (code "147") (name "unconnected-(U100E-QH[5]-Pad11)") (class "Default")
      (node (ref "U100") (pin "11") (pinfunction "QH[5]_11") (pintype "output+no_connect"))
    )
    (net (code "148") (name "unconnected-(U100E-QL[2]-Pad39)") (class "Default")
      (node (ref "U100") (pin "39") (pinfunction "QL[2]_39") (pintype "output+no_connect"))
    )
    (net (code "149") (name "unconnected-(U100E-QL[3]-Pad40)") (class "Default")
      (node (ref "U100") (pin "40") (pinfunction "QL[3]_40") (pintype "output+no_connect"))
    )
    (net (code "150") (name "unconnected-(U100E-QL[4]-Pad41)") (class "Default")
      (node (ref "U100") (pin "41") (pinfunction "QL[4]_41") (pintype "output+no_connect"))
    )
    (net (code "151") (name "unconnected-(U100E-QL[5]-Pad42)") (class "Default")
      (node (ref "U100") (pin "42") (pinfunction "QL[5]_42") (pintype "output+no_connect"))
    )
    (net (code "152") (name "unconnected-(U100E-Reserved-Pad174)") (class "Default")
      (node (ref "U100") (pin "174") (pinfunction "Reserved_174") (pintype "input+no_connect"))
    )
    (net (code "153") (name "unconnected-(U100E-Reserved-Pad175)") (class "Default")
      (node (ref "U100") (pin "175") (pinfunction "Reserved_175") (pintype "input+no_connect"))
    )
    (net (code "154") (name "unconnected-(U100E-TEST[1]-Pad85)") (class "Default")
      (node (ref "U100") (pin "85") (pinfunction "TEST[1]_85") (pintype "input+no_connect"))
    )
    (net (code "155") (name "unconnected-(U100E-TEST[2]-Pad86)") (class "Default")
      (node (ref "U100") (pin "86") (pinfunction "TEST[2]_86") (pintype "input+no_connect"))
    )
    (net (code "156") (name "unconnected-(U100E-T[1]-Pad88)") (class "Default")
      (node (ref "U100") (pin "88") (pinfunction "T[1]_88") (pintype "input+no_connect"))
    )
    (net (code "157") (name "unconnected-(U100E-T[2]-Pad89)") (class "Default")
      (node (ref "U100") (pin "89") (pinfunction "T[2]_89") (pintype "input+no_connect"))
    )
    (net (code "158") (name "unconnected-(U100E-T[3]-Pad90)") (class "Default")
      (node (ref "U100") (pin "90") (pinfunction "T[3]_90") (pintype "input+no_connect"))
    )
    (net (code "159") (name "unconnected-(U100E-T[4]-Pad173)") (class "Default")
      (node (ref "U100") (pin "173") (pinfunction "T[4]_173") (pintype "input+no_connect"))
    )
    (net (code "160") (name "unconnected-(U100E-T[5]-Pad172)") (class "Default")
      (node (ref "U100") (pin "172") (pinfunction "T[5]_172") (pintype "input+no_connect"))
    )
  )
)
